# regulator.net
KiCad netlist of a schematic drawn in Altium Designer
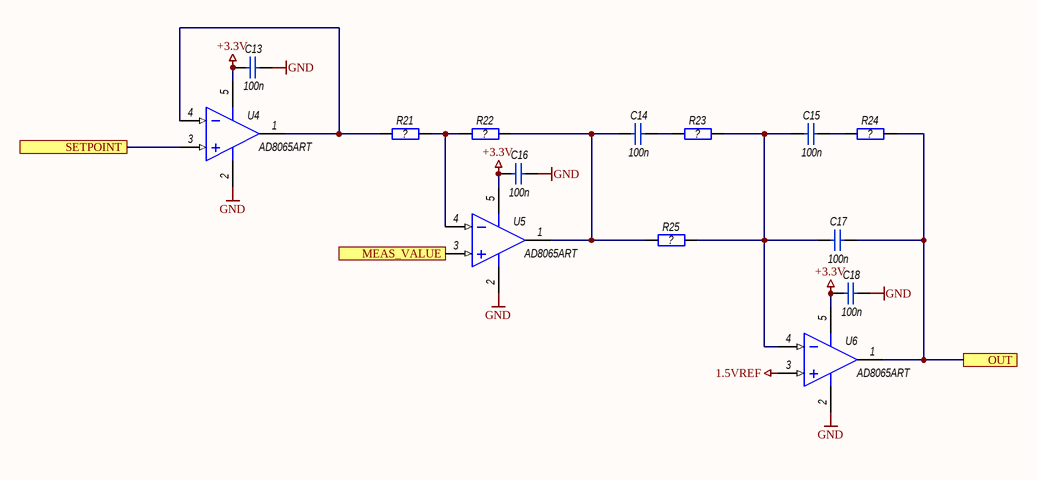
[diagram p0: regulator.SchDoc]

(export (version "E")
  (design (tool "Eeschema 10.0.6"))
  (components
    (comp (ref "C13")
      (value "100n")
      (footprint "CAP_0805")
      (description "Конденсатор")
      (libsource (lib "SCH_LIB") (part "Capacitor"))
    )
    (comp (ref "C14")
      (value "100n")
      (footprint "CAP_0805")
      (description "Конденсатор")
      (libsource (lib "SCH_LIB") (part "Capacitor"))
    )
    (comp (ref "C15")
      (value "100n")
      (footprint "CAP_0805")
      (description "Конденсатор")
      (libsource (lib "SCH_LIB") (part "Capacitor"))
    )
    (comp (ref "C16")
      (value "100n")
      (footprint "CAP_0805")
      (description "Конденсатор")
      (libsource (lib "SCH_LIB") (part "Capacitor"))
    )
    (comp (ref "C17")
      (value "100n")
      (footprint "CAP_0805")
      (description "Конденсатор")
      (libsource (lib "SCH_LIB") (part "Capacitor"))
    )
    (comp (ref "C18")
      (value "100n")
      (footprint "CAP_0805")
      (description "Конденсатор")
      (libsource (lib "SCH_LIB") (part "Capacitor"))
    )
    (comp (ref "R21")
      (value "?")
      (footprint "RES_0805")
      (description "Резистор")
      (libsource (lib "SCH_LIB") (part "Resisitor"))
    )
    (comp (ref "R22")
      (value "?")
      (footprint "RES_0805")
      (description "Резистор")
      (libsource (lib "SCH_LIB") (part "Resisitor"))
    )
    (comp (ref "R23")
      (value "?")
      (footprint "RES_0805")
      (description "Резистор")
      (libsource (lib "SCH_LIB") (part "Resisitor"))
    )
    (comp (ref "R24")
      (value "?")
      (footprint "RES_0805")
      (description "Резистор")
      (libsource (lib "SCH_LIB") (part "Resisitor"))
    )
    (comp (ref "R25")
      (value "?")
      (footprint "RES_0805")
      (description "Резистор")
      (libsource (lib "SCH_LIB") (part "Resisitor"))
    )
    (comp (ref "U4")
      (value "AD8065ART")
      (footprint "sot235")
      (description "Операционный усилитель")
      (libsource (lib "SCH_LIB") (part "OPAMP SOT235"))
    )
    (comp (ref "U5")
      (value "AD8065ART")
      (footprint "sot235")
      (description "Операционный усилитель")
      (libsource (lib "SCH_LIB") (part "OPAMP SOT235"))
    )
    (comp (ref "U6")
      (value "AD8065ART")
      (footprint "sot235")
      (description "Операционный усилитель")
      (libsource (lib "SCH_LIB") (part "OPAMP SOT235"))
    )
  )
  (nets
    (net (code "1") (name "+3.3V") (class "Default")
      (node (ref "C13") (pin "1") (pinfunction "1_1") (pintype "passive"))
      (node (ref "C16") (pin "1") (pinfunction "1_1") (pintype "passive"))
      (node (ref "C18") (pin "1") (pinfunction "1_1") (pintype "passive"))
      (node (ref "U4") (pin "5") (pinfunction "V+_5") (pintype "power_in"))
      (node (ref "U5") (pin "5") (pinfunction "V+_5") (pintype "power_in"))
      (node (ref "U6") (pin "5") (pinfunction "V+_5") (pintype "power_in"))
    )
    (net (code "2") (name "/MEAS_VALUE") (class "Default")
      (node (ref "U5") (pin "3") (pinfunction "IN+_3") (pintype "input"))
    )
    (net (code "3") (name "/OUT") (class "Default")
      (node (ref "C17") (pin "2") (pinfunction "2_2") (pintype "passive"))
      (node (ref "R24") (pin "2") (pinfunction "2_2") (pintype "passive"))
      (node (ref "U6") (pin "1") (pinfunction "OUT_1") (pintype "open_collector"))
    )
    (net (code "4") (name "/SETPOINT") (class "Default")
      (node (ref "U4") (pin "3") (pinfunction "IN+_3") (pintype "input"))
    )
    (net (code "5") (name "1.5VREF") (class "Default")
      (node (ref "U6") (pin "3") (pinfunction "IN+_3") (pintype "input"))
    )
    (net (code "6") (name "GND") (class "Default")
      (node (ref "C13") (pin "2") (pinfunction "2_2") (pintype "passive"))
      (node (ref "C16") (pin "2") (pinfunction "2_2") (pintype "passive"))
      (node (ref "C18") (pin "2") (pinfunction "2_2") (pintype "passive"))
      (node (ref "U4") (pin "2") (pinfunction "V-_2") (pintype "power_in"))
      (node (ref "U5") (pin "2") (pinfunction "V-_2") (pintype "power_in"))
      (node (ref "U6") (pin "2") (pinfunction "V-_2") (pintype "power_in"))
    )
    (net (code "7") (name "Net-(C14-Pad2)") (class "Default")
      (node (ref "C14") (pin "2") (pinfunction "2_2") (pintype "passive"))
      (node (ref "R23") (pin "1") (pinfunction "1_1") (pintype "passive"))
    )
    (net (code "8") (name "Net-(C15-Pad2)") (class "Default")
      (node (ref "C15") (pin "2") (pinfunction "2_2") (pintype "passive"))
      (node (ref "R24") (pin "1") (pinfunction "1_1") (pintype "passive"))
    )
    (net (code "9") (name "Net-(U4-IN-)") (class "Default")
      (node (ref "R21") (pin "1") (pinfunction "1_1") (pintype "passive"))
      (node (ref "U4") (pin "1") (pinfunction "OUT_1") (pintype "open_collector"))
      (node (ref "U4") (pin "4") (pinfunction "IN-_4") (pintype "input"))
    )
    (net (code "10") (name "Net-(U5-IN-)") (class "Default")
      (node (ref "R21") (pin "2") (pinfunction "2_2") (pintype "passive"))
      (node (ref "R22") (pin "1") (pinfunction "1_1") (pintype "passive"))
      (node (ref "U5") (pin "4") (pinfunction "IN-_4") (pintype "input"))
    )
    (net (code "11") (name "Net-(U5-OUT)") (class "Default")
      (node (ref "C14") (pin "1") (pinfunction "1_1") (pintype "passive"))
      (node (ref "R22") (pin "2") (pinfunction "2_2") (pintype "passive"))
      (node (ref "R25") (pin "1") (pinfunction "1_1") (pintype "passive"))
      (node (ref "U5") (pin "1") (pinfunction "OUT_1") (pintype "open_collector"))
    )
    (net (code "12") (name "Net-(U6-IN-)") (class "Default")
      (node (ref "C15") (pin "1") (pinfunction "1_1") (pintype "passive"))
      (node (ref "C17") (pin "1") (pinfunction "1_1") (pintype "passive"))
      (node (ref "R23") (pin "2") (pinfunction "2_2") (pintype "passive"))
      (node (ref "R25") (pin "2") (pinfunction "2_2") (pintype "passive"))
      (node (ref "U6") (pin "4") (pinfunction "IN-_4") (pintype "input"))
    )
  )
)
